# Nano-RS485_RJ45-GW-v1.net
KiCad netlist of a schematic drawn in EAGLE
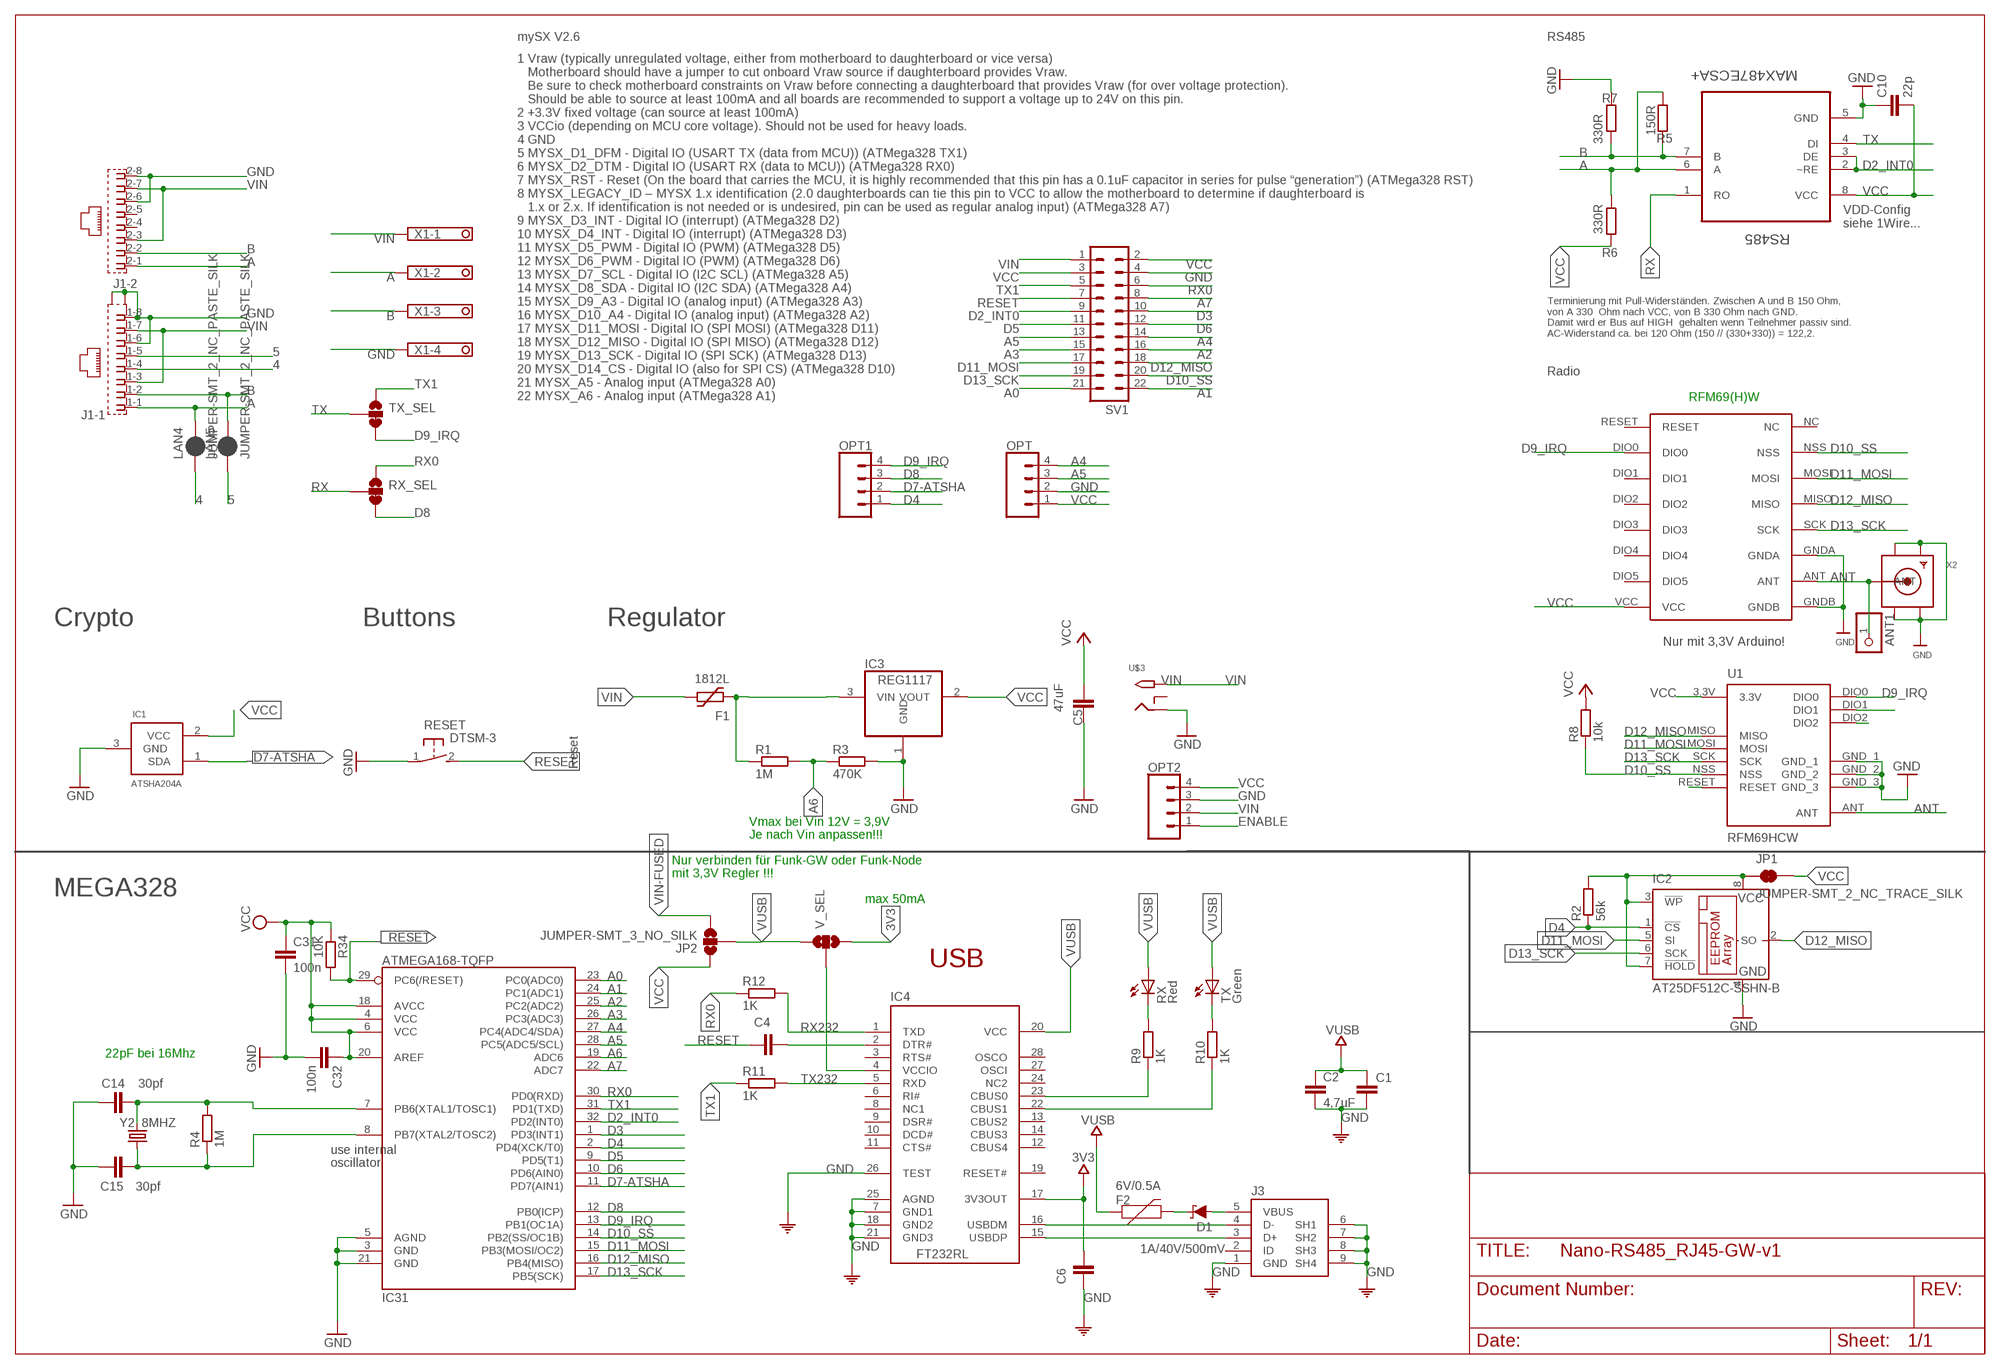
[diagram p0: schematic, sheet 1]

(export (version "E")
  (design (tool "Eeschema 10.0.6"))
  (components
    (comp (ref "ANT1")
      (value "PINHD-1X1")
      (footprint "eagle-import:1X01")
      (libsource (lib "eagle-import") (part "PINHD-1X1"))
    )
    (comp (ref "C1")
      (value "100nF")
      (footprint "eagle-import:C0805")
      (libsource (lib "eagle-import") (part "resistor_348_C-EUC0805"))
    )
    (comp (ref "C2")
      (value "4,7uF")
      (footprint "eagle-import:C1206")
      (libsource (lib "eagle-import") (part "resistor_348_C-EUC1206"))
    )
    (comp (ref "C4")
      (value "100nF")
      (footprint "eagle-import:C0805")
      (libsource (lib "eagle-import") (part "resistor_348_C-EUC0805"))
    )
    (comp (ref "C5")
      (value "47uF")
      (footprint "eagle-import:C1206")
      (libsource (lib "eagle-import") (part "resistor_348_C-EUC1206"))
    )
    (comp (ref "C6")
      (value "100nF")
      (footprint "eagle-import:C0805")
      (libsource (lib "eagle-import") (part "resistor_348_C-EUC0805"))
    )
    (comp (ref "C10")
      (value "22p")
      (footprint "eagle-import:C0805")
      (libsource (lib "eagle-import") (part "C-EUC0805"))
    )
    (comp (ref "C14")
      (value "30pf")
      (footprint "eagle-import:0805")
      (libsource (lib "eagle-import") (part "CAP0805"))
    )
    (comp (ref "C15")
      (value "30pf")
      (footprint "eagle-import:0805")
      (libsource (lib "eagle-import") (part "CAP0805"))
    )
    (comp (ref "C31")
      (value "100n")
      (footprint "eagle-import:C0805")
      (libsource (lib "eagle-import") (part "C-EUC0805"))
    )
    (comp (ref "C32")
      (value "100n")
      (footprint "eagle-import:C0805")
      (libsource (lib "eagle-import") (part "C-EUC0805"))
    )
    (comp (ref "D1")
      (value "1A/40V/500mV")
      (footprint "eagle-import:SMA-DIODE")
      (libsource (lib "eagle-import") (part "DIODE-SCHOTTKY-SS14"))
    )
    (comp (ref "F1")
      (value "1812L")
      (footprint "eagle-import:1812L")
      (libsource (lib "eagle-import") (part "1812L"))
    )
    (comp (ref "F2")
      (value "6V/0.5A")
      (footprint "eagle-import:1206")
      (libsource (lib "eagle-import") (part "PPTC_HALF-AMP"))
    )
    (comp (ref "IC1")
      (value "ATSHA204A")
      (footprint "eagle-import:SOT23")
      (libsource (lib "eagle-import") (part "ATSHA204A"))
    )
    (comp (ref "IC2")
      (value "AT25DF512C-SSHN-B")
      (footprint "eagle-import:SO-08")
      (fields (field (name "MF") "MICROCHIP") (field (name "MPN") "25AA080/SN"))
      (libsource (lib "eagle-import") (part "25SNAA080"))
    )
    (comp (ref "IC3")
      (value "REG1117")
      (footprint "eagle-import:SOT223")
      (libsource (lib "eagle-import") (part "REG1117"))
    )
    (comp (ref "IC4")
      (value "FT232RL")
      (footprint "eagle-import:SSOP28")
      (libsource (lib "eagle-import") (part "0226_FT232RL"))
    )
    (comp (ref "IC31")
      (value "ATMEGA168-TQFP")
      (footprint "eagle-import:TQFP32-08")
      (libsource (lib "eagle-import") (part "ATMEGA168-TQFP"))
    )
    (comp (ref "J1")
      (value "RJ45_2X_NARROW_SHILDPINS_NOCASE")
      (footprint "eagle-import:RJ45_2X_NARROW_SHILDPINS_NOCASE")
      (libsource (lib "eagle-import") (part "RJ45_2X_NARROW_SHILDPINS_NOCASE"))
    )
    (comp (ref "J3")
      (value "0219_14850")
      (footprint "eagle-import:USB-MINI-B_2")
      (fields (field (name "PART_NUMBER") "14850"))
      (libsource (lib "eagle-import") (part "0219_14850"))
    )
    (comp (ref "JP1")
      (value "JUMPER-SMT_2_NC_TRACE_SILK")
      (footprint "eagle-import:SMT-JUMPER_2_NC_TRACE_SILK")
      (libsource (lib "eagle-import") (part "JUMPER-SMT_2_NC_TRACE_SILK"))
    )
    (comp (ref "JP2")
      (value "JUMPER-SMT_3_NO_SILK")
      (footprint "eagle-import:SMT-JUMPER_3_NO_SILK")
      (libsource (lib "eagle-import") (part "JUMPER-SMT_3_NO_SILK"))
    )
    (comp (ref "LAN4")
      (value "JUMPER-SMT_2_NC_PASTE_SILK")
      (footprint "eagle-import:SMT-JUMPER_2_NC_PASTE_SILK")
      (libsource (lib "eagle-import") (part "JUMPER-SMT_2_NC_PASTE_SILK"))
    )
    (comp (ref "LAN5")
      (value "JUMPER-SMT_2_NC_PASTE_SILK")
      (footprint "eagle-import:SMT-JUMPER_2_NC_PASTE_SILK")
      (libsource (lib "eagle-import") (part "JUMPER-SMT_2_NC_PASTE_SILK"))
    )
    (comp (ref "OPT")
      (value "CONN_04")
      (footprint "eagle-import:1X04")
      (libsource (lib "eagle-import") (part "CONN_04"))
    )
    (comp (ref "OPT1")
      (value "CONN_04")
      (footprint "eagle-import:1X04")
      (libsource (lib "eagle-import") (part "CONN_04"))
    )
    (comp (ref "OPT2")
      (value "CONN_04")
      (footprint "eagle-import:1X04")
      (libsource (lib "eagle-import") (part "CONN_04"))
    )
    (comp (ref "R1")
      (value "1M")
      (footprint "eagle-import:M0805")
      (libsource (lib "eagle-import") (part "R-EU_M0805"))
    )
    (comp (ref "R2")
      (value "56k")
      (footprint "eagle-import:M0805")
      (libsource (lib "eagle-import") (part "resistor_R-EU_M0805"))
    )
    (comp (ref "R3")
      (value "470K")
      (footprint "eagle-import:R0805")
      (libsource (lib "eagle-import") (part "R-EU_R0805"))
    )
    (comp (ref "R4")
      (value "1M")
      (footprint "eagle-import:M0805")
      (libsource (lib "eagle-import") (part "R-EU_M0805"))
    )
    (comp (ref "R5")
      (value "150R")
      (footprint "eagle-import:R0805")
      (libsource (lib "eagle-import") (part "R-EU_R0805"))
    )
    (comp (ref "R6")
      (value "330R")
      (footprint "eagle-import:R0805")
      (libsource (lib "eagle-import") (part "R-EU_R0805"))
    )
    (comp (ref "R7")
      (value "330R")
      (footprint "eagle-import:R0805")
      (libsource (lib "eagle-import") (part "R-EU_R0805"))
    )
    (comp (ref "R8")
      (value "10k")
      (footprint "eagle-import:M0805")
      (libsource (lib "eagle-import") (part "R-EU_M0805"))
    )
    (comp (ref "R9")
      (value "1K")
      (footprint "eagle-import:R0805")
      (libsource (lib "eagle-import") (part "resistor_348_R-EU_R0805"))
    )
    (comp (ref "R10")
      (value "1K")
      (footprint "eagle-import:R0805")
      (libsource (lib "eagle-import") (part "resistor_348_R-EU_R0805"))
    )
    (comp (ref "R11")
      (value "1K")
      (footprint "eagle-import:R0805")
      (libsource (lib "eagle-import") (part "resistor_348_R-EU_R0805"))
    )
    (comp (ref "R12")
      (value "1K")
      (footprint "eagle-import:R0805")
      (libsource (lib "eagle-import") (part "resistor_348_R-EU_R0805"))
    )
    (comp (ref "R34")
      (value "10K")
      (footprint "eagle-import:R0805")
      (libsource (lib "eagle-import") (part "R-EU_R0805"))
    )
    (comp (ref "RESET")
      (value "DTSM-3")
      (footprint "eagle-import:DTSM-3")
      (libsource (lib "eagle-import") (part "DTSM-3"))
    )
    (comp (ref "RFM69W")
      (value "RFM69HW")
      (footprint "eagle-import:RFM")
      (libsource (lib "eagle-import") (part "RFM69HW"))
    )
    (comp (ref "RS485")
      (value "MAX487ECSA+")
      (footprint "eagle-import:SOIC127P600X175-8N")
      (libsource (lib "eagle-import") (part "MAX487ECSA+"))
    )
    (comp (ref "RX")
      (value "Red")
      (footprint "eagle-import:CHIPLED_0805")
      (fields (field (name "PART_NUMBER") "KTP-2012SURCK"))
      (libsource (lib "eagle-import") (part "0181_KTP-2012SURCK"))
    )
    (comp (ref "RX_SEL")
      (value "JUMPER-SMT_3_1-NC_TRACE_SILK")
      (footprint "eagle-import:SMT-JUMPER_3_1-NC_TRACE_SILK")
      (libsource (lib "eagle-import") (part "JUMPER-SMT_3_1-NC_TRACE_SILK"))
    )
    (comp (ref "SV1")
      (value "MA11-2")
      (footprint "eagle-import:MA11-2")
      (libsource (lib "eagle-import") (part "MA11-2"))
    )
    (comp (ref "TX")
      (value "Green")
      (footprint "eagle-import:CHIPLED_0805")
      (fields (field (name "PART_NUMBER") "KPT-2012SGC"))
      (libsource (lib "eagle-import") (part "0043_KPT-2012SGC"))
    )
    (comp (ref "TX_SEL")
      (value "JUMPER-SMT_3_1-NC_TRACE_SILK")
      (footprint "eagle-import:SMT-JUMPER_3_1-NC_TRACE_SILK")
      (libsource (lib "eagle-import") (part "JUMPER-SMT_3_1-NC_TRACE_SILK"))
    )
    (comp (ref "U$3")
      (value "2.1MMJACKTHM")
      (footprint "eagle-import:PJ-102A")
      (libsource (lib "eagle-import") (part "2.1MMJACKTHM"))
    )
    (comp (ref "U1")
      (value "RFM69HCW")
      (footprint "eagle-import:RFM69HCW-XXXS2")
      (libsource (lib "eagle-import") (part "RFM69HCW"))
    )
    (comp (ref "V_SEL")
      (value "JUMPER-SMT_3_NO_SILK")
      (footprint "eagle-import:SMT-JUMPER_3_NO_SILK")
      (libsource (lib "eagle-import") (part "JUMPER-SMT_3_NO_SILK"))
    )
    (comp (ref "X1")
      (value "1751264")
      (footprint "eagle-import:1751264")
      (libsource (lib "eagle-import") (part "1751264"))
    )
    (comp (ref "X2")
      (value "SMACONNECTOR_EDGE")
      (footprint "eagle-import:SMA_EDGELAUNCH")
      (libsource (lib "eagle-import") (part "SMACONNECTOR_EDGE"))
    )
    (comp (ref "Y2")
      (value "8MHZ")
      (footprint "eagle-import:CRYSTAL-TXC-7A")
      (libsource (lib "eagle-import") (part "CRYSTALTXC-7A"))
    )
  )
  (nets
    (net (code "1") (name "/4") (class "Default")
      (node (ref "J1") (pin "1-4") (pinfunction "4_1-4") (pintype "passive"))
      (node (ref "LAN4") (pin "1") (pinfunction "1_1") (pintype "passive"))
    )
    (net (code "2") (name "/5") (class "Default")
      (node (ref "J1") (pin "1-5") (pinfunction "5_1-5") (pintype "passive"))
      (node (ref "LAN5") (pin "1") (pinfunction "1_1") (pintype "passive"))
    )
    (net (code "3") (name "/A") (class "Default")
      (node (ref "J1") (pin "1-1") (pinfunction "1_1-1") (pintype "passive"))
      (node (ref "J1") (pin "2-1") (pinfunction "1_2-1") (pintype "passive"))
      (node (ref "LAN4") (pin "2") (pinfunction "2_2") (pintype "passive"))
      (node (ref "R5") (pin "1") (pinfunction "1_1") (pintype "passive"))
      (node (ref "R6") (pin "2") (pinfunction "2_2") (pintype "passive"))
      (node (ref "RS485") (pin "6") (pinfunction "A_6") (pintype "bidirectional"))
      (node (ref "X1") (pin "2") (pinfunction "K_2") (pintype "passive"))
    )
    (net (code "4") (name "/A0") (class "Default")
      (node (ref "IC31") (pin "23") (pinfunction "PC0(ADC0)_23") (pintype "bidirectional"))
      (node (ref "SV1") (pin "21") (pinfunction "21_21") (pintype "passive"))
    )
    (net (code "5") (name "/A1") (class "Default")
      (node (ref "IC31") (pin "24") (pinfunction "PC1(ADC1)_24") (pintype "bidirectional"))
      (node (ref "SV1") (pin "22") (pinfunction "22_22") (pintype "passive"))
    )
    (net (code "6") (name "/A2") (class "Default")
      (node (ref "IC31") (pin "25") (pinfunction "PC2(ADC2)_25") (pintype "bidirectional"))
      (node (ref "SV1") (pin "16") (pinfunction "16_16") (pintype "passive"))
    )
    (net (code "7") (name "/A3") (class "Default")
      (node (ref "IC31") (pin "26") (pinfunction "PC3(ADC3)_26") (pintype "bidirectional"))
      (node (ref "SV1") (pin "15") (pinfunction "15_15") (pintype "passive"))
    )
    (net (code "8") (name "/A4") (class "Default")
      (node (ref "IC31") (pin "27") (pinfunction "PC4(ADC4/SDA)_27") (pintype "bidirectional"))
      (node (ref "OPT") (pin "4") (pinfunction "4_4") (pintype "passive"))
      (node (ref "SV1") (pin "14") (pinfunction "14_14") (pintype "passive"))
    )
    (net (code "9") (name "/A5") (class "Default")
      (node (ref "IC31") (pin "28") (pinfunction "PC5(ADC5/SCL)_28") (pintype "bidirectional"))
      (node (ref "OPT") (pin "3") (pinfunction "3_3") (pintype "passive"))
      (node (ref "SV1") (pin "13") (pinfunction "13_13") (pintype "passive"))
    )
    (net (code "10") (name "/A7") (class "Default")
      (node (ref "IC31") (pin "22") (pinfunction "ADC7_22") (pintype "bidirectional"))
      (node (ref "SV1") (pin "8") (pinfunction "8_8") (pintype "passive"))
    )
    (net (code "11") (name "/ANT") (class "Default")
      (node (ref "ANT1") (pin "1") (pinfunction "1_1") (pintype "passive"))
      (node (ref "RFM69W") (pin "ANT") (pinfunction "ANT_ANT") (pintype "bidirectional"))
      (node (ref "U1") (pin "ANT") (pinfunction "ANT_ANT") (pintype "passive"))
      (node (ref "X2") (pin "P") (pinfunction "ANT_P") (pintype "bidirectional"))
    )
    (net (code "12") (name "/B") (class "Default")
      (node (ref "J1") (pin "1-2") (pinfunction "2_1-2") (pintype "passive"))
      (node (ref "J1") (pin "2-2") (pinfunction "2_2-2") (pintype "passive"))
      (node (ref "LAN5") (pin "2") (pinfunction "2_2") (pintype "passive"))
      (node (ref "R5") (pin "2") (pinfunction "2_2") (pintype "passive"))
      (node (ref "R7") (pin "1") (pinfunction "1_1") (pintype "passive"))
      (node (ref "RS485") (pin "7") (pinfunction "B_7") (pintype "bidirectional"))
      (node (ref "X1") (pin "3") (pinfunction "K_3") (pintype "passive"))
    )
    (net (code "13") (name "/D2_INT0") (class "Default")
      (node (ref "IC31") (pin "32") (pinfunction "PD2(INT0)_32") (pintype "bidirectional"))
      (node (ref "RS485") (pin "2") (pinfunction "~{RE}_2") (pintype "input"))
      (node (ref "RS485") (pin "3") (pinfunction "DE_3") (pintype "input"))
      (node (ref "SV1") (pin "9") (pinfunction "9_9") (pintype "passive"))
    )
    (net (code "14") (name "/D3") (class "Default")
      (node (ref "IC31") (pin "1") (pinfunction "PD3(INT1)_1") (pintype "bidirectional"))
      (node (ref "SV1") (pin "10") (pinfunction "10_10") (pintype "passive"))
    )
    (net (code "15") (name "/D5") (class "Default")
      (node (ref "IC31") (pin "9") (pinfunction "PD5(T1)_9") (pintype "bidirectional"))
      (node (ref "SV1") (pin "11") (pinfunction "11_11") (pintype "passive"))
    )
    (net (code "16") (name "/D6") (class "Default")
      (node (ref "IC31") (pin "10") (pinfunction "PD6(AIN0)_10") (pintype "bidirectional"))
      (node (ref "SV1") (pin "12") (pinfunction "12_12") (pintype "passive"))
    )
    (net (code "17") (name "/D7-ATSHA") (class "Default")
      (node (ref "IC1") (pin "1") (pinfunction "SDA_1") (pintype "bidirectional"))
      (node (ref "IC31") (pin "11") (pinfunction "PD7(AIN1)_11") (pintype "bidirectional"))
      (node (ref "OPT1") (pin "2") (pinfunction "2_2") (pintype "passive"))
    )
    (net (code "18") (name "/D8") (class "Default")
      (node (ref "IC31") (pin "12") (pinfunction "PB0(ICP)_12") (pintype "bidirectional"))
      (node (ref "OPT1") (pin "3") (pinfunction "3_3") (pintype "passive"))
      (node (ref "RX_SEL") (pin "3") (pinfunction "3_3") (pintype "passive"))
    )
    (net (code "19") (name "/D9_IRQ") (class "Default")
      (node (ref "IC31") (pin "13") (pinfunction "PB1(OC1A)_13") (pintype "bidirectional"))
      (node (ref "OPT1") (pin "4") (pinfunction "4_4") (pintype "passive"))
      (node (ref "RFM69W") (pin "DIO0") (pinfunction "DIO0_DIO0") (pintype "bidirectional"))
      (node (ref "TX_SEL") (pin "3") (pinfunction "3_3") (pintype "passive"))
      (node (ref "U1") (pin "DIO0") (pinfunction "DIO0_DIO0") (pintype "bidirectional"))
    )
    (net (code "20") (name "/D10_SS") (class "Default")
      (node (ref "IC31") (pin "14") (pinfunction "PB2(SS/OC1B)_14") (pintype "bidirectional"))
      (node (ref "R8") (pin "1") (pinfunction "1_1") (pintype "passive"))
      (node (ref "RFM69W") (pin "NSS") (pinfunction "NSS_NSS") (pintype "bidirectional"))
      (node (ref "SV1") (pin "20") (pinfunction "20_20") (pintype "passive"))
      (node (ref "U1") (pin "NSS") (pinfunction "NSS_NSS") (pintype "input"))
    )
    (net (code "21") (name "/ENABLE") (class "Default")
      (node (ref "OPT2") (pin "1") (pinfunction "1_1") (pintype "passive"))
    )
    (net (code "22") (name "/RX232") (class "Default")
      (node (ref "IC4") (pin "1") (pinfunction "TXD_1") (pintype "output"))
      (node (ref "R12") (pin "2") (pinfunction "2_2") (pintype "passive"))
    )
    (net (code "23") (name "/TX") (class "Default")
      (node (ref "RS485") (pin "4") (pinfunction "DI_4") (pintype "input"))
      (node (ref "TX_SEL") (pin "2") (pinfunction "2_2") (pintype "passive"))
    )
    (net (code "24") (name "/TX232") (class "Default")
      (node (ref "IC4") (pin "5") (pinfunction "RXD_5") (pintype "input"))
      (node (ref "R11") (pin "2") (pinfunction "2_2") (pintype "passive"))
    )
    (net (code "25") (name "3V3") (class "Default")
      (node (ref "C6") (pin "2") (pinfunction "2_2") (pintype "passive"))
      (node (ref "IC4") (pin "17") (pinfunction "3V3OUT_17") (pintype "power_in"))
      (node (ref "V_SEL") (pin "3") (pinfunction "3_3") (pintype "passive"))
    )
    (net (code "26") (name "A6") (class "Default")
      (node (ref "IC31") (pin "19") (pinfunction "ADC6_19") (pintype "bidirectional"))
      (node (ref "R1") (pin "2") (pinfunction "2_2") (pintype "passive"))
      (node (ref "R3") (pin "1") (pinfunction "1_1") (pintype "passive"))
    )
    (net (code "27") (name "COM") (class "Default")
      (node (ref "C1") (pin "2") (pinfunction "2_2") (pintype "passive"))
      (node (ref "C10") (pin "1") (pinfunction "1_1") (pintype "passive"))
      (node (ref "C14") (pin "1") (pinfunction "1_1") (pintype "passive"))
      (node (ref "C15") (pin "1") (pinfunction "1_1") (pintype "passive"))
      (node (ref "C2") (pin "2") (pinfunction "2_2") (pintype "passive"))
      (node (ref "C31") (pin "2") (pinfunction "2_2") (pintype "passive"))
      (node (ref "C32") (pin "2") (pinfunction "2_2") (pintype "passive"))
      (node (ref "C5") (pin "1") (pinfunction "1_1") (pintype "passive"))
      (node (ref "C6") (pin "1") (pinfunction "1_1") (pintype "passive"))
      (node (ref "IC1") (pin "3") (pinfunction "GND_3") (pintype "bidirectional"))
      (node (ref "IC2") (pin "4") (pinfunction "GND_4") (pintype "power_in"))
      (node (ref "IC3") (pin "1") (pinfunction "GND_1") (pintype "power_in"))
      (node (ref "IC31") (pin "21") (pinfunction "GND_21") (pintype "bidirectional"))
      (node (ref "IC31") (pin "3") (pinfunction "GND_3") (pintype "bidirectional"))
      (node (ref "IC31") (pin "5") (pinfunction "AGND_5") (pintype "bidirectional"))
      (node (ref "IC4") (pin "18") (pinfunction "GND2_18") (pintype "power_in"))
      (node (ref "IC4") (pin "21") (pinfunction "GND3_21") (pintype "power_in"))
      (node (ref "IC4") (pin "25") (pinfunction "AGND_25") (pintype "power_in"))
      (node (ref "IC4") (pin "26") (pinfunction "TEST_26") (pintype "bidirectional"))
      (node (ref "IC4") (pin "7") (pinfunction "GND1_7") (pintype "power_in"))
      (node (ref "J1") (pin "1-6") (pinfunction "6_1-6") (pintype "passive"))
      (node (ref "J1") (pin "1-8") (pinfunction "8_1-8") (pintype "passive"))
      (node (ref "J1") (pin "2-6") (pinfunction "6_2-6") (pintype "passive"))
      (node (ref "J1") (pin "2-8") (pinfunction "8_2-8") (pintype "passive"))
      (node (ref "J1") (pin "G1") (pinfunction "S1_G1") (pintype "passive"))
      (node (ref "J1") (pin "G3") (pinfunction "S2_G3") (pintype "passive"))
      (node (ref "J3") (pin "1") (pinfunction "GND_1") (pintype "passive"))
      (node (ref "J3") (pin "6") (pinfunction "SH1_6") (pintype "passive"))
      (node (ref "J3") (pin "7") (pinfunction "SH2_7") (pintype "passive"))
      (node (ref "J3") (pin "8") (pinfunction "SH3_8") (pintype "passive"))
      (node (ref "J3") (pin "9") (pinfunction "SH4_9") (pintype "passive"))
      (node (ref "OPT") (pin "2") (pinfunction "2_2") (pintype "passive"))
      (node (ref "OPT2") (pin "3") (pinfunction "3_3") (pintype "passive"))
      (node (ref "R3") (pin "2") (pinfunction "2_2") (pintype "passive"))
      (node (ref "R7") (pin "2") (pinfunction "2_2") (pintype "passive"))
      (node (ref "RESET") (pin "1") (pinfunction "1_1") (pintype "passive"))
      (node (ref "RFM69W") (pin "GNDA") (pinfunction "GNDA_GNDA") (pintype "bidirectional"))
      (node (ref "RFM69W") (pin "GNDB") (pinfunction "GNDB_GNDB") (pintype "bidirectional"))
      (node (ref "RS485") (pin "5") (pinfunction "GND_5") (pintype "passive"))
      (node (ref "SV1") (pin "4") (pinfunction "4_4") (pintype "passive"))
      (node (ref "U$3") (pin "RING") (pinfunction "RING_RING") (pintype "bidirectional"))
      (node (ref "U1") (pin "GND_1") (pinfunction "GND_1_GND_1") (pintype "power_in"))
      (node (ref "U1") (pin "GND_2") (pinfunction "GND_2_GND_2") (pintype "power_in"))
      (node (ref "U1") (pin "GND_3") (pinfunction "GND_3_GND_3") (pintype "power_in"))
      (node (ref "X1") (pin "4") (pinfunction "K_4") (pintype "passive"))
      (node (ref "X2") (pin "GND@1") (pinfunction "GND4_GND@1") (pintype "power_in"))
      (node (ref "X2") (pin "GND@2") (pinfunction "GND3_GND@2") (pintype "power_in"))
      (node (ref "X2") (pin "GND@3") (pinfunction "GND2_GND@3") (pintype "power_in"))
      (node (ref "X2") (pin "GND@4") (pinfunction "GND1_GND@4") (pintype "power_in"))
    )
    (net (code "28") (name "D4") (class "Default")
      (node (ref "IC2") (pin "1") (pinfunction "~{CS}_1") (pintype "input"))
      (node (ref "IC31") (pin "2") (pinfunction "PD4(XCK/T0)_2") (pintype "bidirectional"))
      (node (ref "OPT1") (pin "1") (pinfunction "1_1") (pintype "passive"))
      (node (ref "R2") (pin "1") (pinfunction "1_1") (pintype "passive"))
    )
    (net (code "29") (name "D11_MOSI") (class "Default")
      (node (ref "IC2") (pin "5") (pinfunction "SI_5") (pintype "input"))
      (node (ref "IC31") (pin "15") (pinfunction "PB3(MOSI/OC2)_15") (pintype "bidirectional"))
      (node (ref "RFM69W") (pin "MOSI") (pinfunction "MOSI_MOSI") (pintype "bidirectional"))
      (node (ref "SV1") (pin "17") (pinfunction "17_17") (pintype "passive"))
      (node (ref "U1") (pin "MOSI") (pinfunction "MOSI_MOSI") (pintype "input"))
    )
    (net (code "30") (name "D12_MISO") (class "Default")
      (node (ref "IC2") (pin "2") (pinfunction "SO_2") (pintype "bidirectional"))
      (node (ref "IC31") (pin "16") (pinfunction "PB4(MISO)_16") (pintype "bidirectional"))
      (node (ref "RFM69W") (pin "MISO") (pinfunction "MISO_MISO") (pintype "bidirectional"))
      (node (ref "SV1") (pin "18") (pinfunction "18_18") (pintype "passive"))
      (node (ref "U1") (pin "MISO") (pinfunction "MISO_MISO") (pintype "bidirectional"))
    )
    (net (code "31") (name "D13_SCK") (class "Default")
      (node (ref "IC2") (pin "6") (pinfunction "SCK_6") (pintype "input"))
      (node (ref "IC31") (pin "17") (pinfunction "PB5(SCK)_17") (pintype "bidirectional"))
      (node (ref "RFM69W") (pin "SCK") (pinfunction "SCK_SCK") (pintype "bidirectional"))
      (node (ref "SV1") (pin "19") (pinfunction "19_19") (pintype "passive"))
      (node (ref "U1") (pin "SCK") (pinfunction "SCK_SCK") (pintype "input"))
    )
    (net (code "32") (name "Net-(D1-PadC)") (class "Default")
      (node (ref "D1") (pin "C") (pinfunction "C_C") (pintype "passive"))
      (node (ref "F2") (pin "2") (pinfunction "2_2") (pintype "bidirectional"))
    )
    (net (code "33") (name "Net-(IC2-VCC)") (class "Default")
      (node (ref "IC2") (pin "3") (pinfunction "~{WP}_3") (pintype "input"))
      (node (ref "IC2") (pin "7") (pinfunction "~{HOLD}_7") (pintype "input"))
      (node (ref "IC2") (pin "8") (pinfunction "VCC_8") (pintype "power_in"))
      (node (ref "JP1") (pin "1") (pinfunction "1_1") (pintype "passive"))
      (node (ref "R2") (pin "2") (pinfunction "2_2") (pintype "passive"))
    )
    (net (code "34") (name "Net-(IC4-CBUS0)") (class "Default")
      (node (ref "IC4") (pin "23") (pinfunction "CBUS0_23") (pintype "bidirectional"))
      (node (ref "R9") (pin "1") (pinfunction "1_1") (pintype "passive"))
    )
    (net (code "35") (name "Net-(IC4-CBUS1)") (class "Default")
      (node (ref "IC4") (pin "22") (pinfunction "CBUS1_22") (pintype "bidirectional"))
      (node (ref "R10") (pin "1") (pinfunction "1_1") (pintype "passive"))
    )
    (net (code "36") (name "Net-(IC4-DTR#)") (class "Default")
      (node (ref "C4") (pin "2") (pinfunction "2_2") (pintype "passive"))
      (node (ref "IC4") (pin "2") (pinfunction "DTR#_2") (pintype "output"))
    )
    (net (code "37") (name "Net-(IC4-USBDM)") (class "Default")
      (node (ref "IC4") (pin "16") (pinfunction "USBDM_16") (pintype "bidirectional"))
      (node (ref "J3") (pin "4") (pinfunction "D-_4") (pintype "bidirectional"))
    )
    (net (code "38") (name "Net-(IC4-USBDP)") (class "Default")
      (node (ref "IC4") (pin "15") (pinfunction "USBDP_15") (pintype "bidirectional"))
      (node (ref "J3") (pin "3") (pinfunction "D+_3") (pintype "bidirectional"))
    )
    (net (code "39") (name "Net-(IC4-VCCIO)") (class "Default")
      (node (ref "IC4") (pin "4") (pinfunction "VCCIO_4") (pintype "power_in"))
      (node (ref "V_SEL") (pin "2") (pinfunction "2_2") (pintype "passive"))
    )
    (net (code "40") (name "Net-(IC31-PB6(XTAL1{slash}TOSC1))") (class "Default")
      (node (ref "C14") (pin "2") (pinfunction "2_2") (pintype "passive"))
      (node (ref "IC31") (pin "7") (pinfunction "PB6(XTAL1/TOSC1)_7") (pintype "bidirectional"))
      (node (ref "R4") (pin "2") (pinfunction "2_2") (pintype "passive"))
      (node (ref "Y2") (pin "P$2") (pinfunction "2_P$2") (pintype "passive"))
    )
    (net (code "41") (name "Net-(IC31-PB7(XTAL2{slash}TOSC2))") (class "Default")
      (node (ref "C15") (pin "2") (pinfunction "2_2") (pintype "passive"))
      (node (ref "IC31") (pin "8") (pinfunction "PB7(XTAL2/TOSC2)_8") (pintype "bidirectional"))
      (node (ref "R4") (pin "1") (pinfunction "1_1") (pintype "passive"))
      (node (ref "Y2") (pin "P$1") (pinfunction "1_P$1") (pintype "passive"))
    )
    (net (code "42") (name "Net-(J3-VBUS)") (class "Default")
      (node (ref "D1") (pin "A") (pinfunction "A_A") (pintype "passive"))
      (node (ref "J3") (pin "5") (pinfunction "VBUS_5") (pintype "power_in"))
    )
    (net (code "43") (name "Net-(R9-Pad2)") (class "Default")
      (node (ref "R9") (pin "2") (pinfunction "2_2") (pintype "passive"))
      (node (ref "RX") (pin "C") (pinfunction "C_C") (pintype "passive"))
    )
    (net (code "44") (name "Net-(R10-Pad2)") (class "Default")
      (node (ref "R10") (pin "2") (pinfunction "2_2") (pintype "passive"))
      (node (ref "TX") (pin "C") (pinfunction "C_C") (pintype "passive"))
    )
    (net (code "45") (name "RESET") (class "Default")
      (node (ref "C4") (pin "1") (pinfunction "1_1") (pintype "passive"))
      (node (ref "IC31") (pin "29") (pinfunction "PC6(/RESET)_29") (pintype "bidirectional"))
      (node (ref "R34") (pin "2") (pinfunction "2_2") (pintype "passive"))
      (node (ref "RESET") (pin "2") (pinfunction "2_2") (pintype "passive"))
      (node (ref "SV1") (pin "7") (pinfunction "7_7") (pintype "passive"))
    )
    (net (code "46") (name "RX") (class "Default")
      (node (ref "RS485") (pin "1") (pinfunction "RO_1") (pintype "output"))
      (node (ref "RX_SEL") (pin "2") (pinfunction "2_2") (pintype "passive"))
    )
    (net (code "47") (name "RX0") (class "Default")
      (node (ref "IC31") (pin "30") (pinfunction "PD0(RXD)_30") (pintype "bidirectional"))
      (node (ref "R12") (pin "1") (pinfunction "1_1") (pintype "passive"))
      (node (ref "RX_SEL") (pin "1") (pinfunction "1_1") (pintype "passive"))
      (node (ref "SV1") (pin "6") (pinfunction "6_6") (pintype "passive"))
    )
    (net (code "48") (name "TX1") (class "Default")
      (node (ref "IC31") (pin "31") (pinfunction "PD1(TXD)_31") (pintype "bidirectional"))
      (node (ref "R11") (pin "1") (pinfunction "1_1") (pintype "passive"))
      (node (ref "SV1") (pin "5") (pinfunction "5_5") (pintype "passive"))
      (node (ref "TX_SEL") (pin "1") (pinfunction "1_1") (pintype "passive"))
    )
    (net (code "49") (name "VCC") (class "Default")
      (node (ref "C10") (pin "2") (pinfunction "2_2") (pintype "passive"))
      (node (ref "C31") (pin "1") (pinfunction "1_1") (pintype "passive"))
      (node (ref "C32") (pin "1") (pinfunction "1_1") (pintype "passive"))
      (node (ref "C5") (pin "2") (pinfunction "2_2") (pintype "passive"))
      (node (ref "IC1") (pin "2") (pinfunction "VCC_2") (pintype "bidirectional"))
      (node (ref "IC3") (pin "2") (pinfunction "VOUT_2") (pintype "output"))
      (node (ref "IC31") (pin "18") (pinfunction "AVCC_18") (pintype "bidirectional"))
      (node (ref "IC31") (pin "20") (pinfunction "AREF_20") (pintype "bidirectional"))
      (node (ref "IC31") (pin "4") (pinfunction "VCC_4") (pintype "bidirectional"))
      (node (ref "IC31") (pin "6") (pinfunction "VCC_6") (pintype "bidirectional"))
      (node (ref "JP1") (pin "2") (pinfunction "2_2") (pintype "passive"))
      (node (ref "JP2") (pin "1") (pinfunction "1_1") (pintype "passive"))
      (node (ref "OPT") (pin "1") (pinfunction "1_1") (pintype "passive"))
      (node (ref "OPT2") (pin "4") (pinfunction "4_4") (pintype "passive"))
      (node (ref "R34") (pin "1") (pinfunction "1_1") (pintype "passive"))
      (node (ref "R6") (pin "1") (pinfunction "1_1") (pintype "passive"))
      (node (ref "R8") (pin "2") (pinfunction "2_2") (pintype "passive"))
      (node (ref "RFM69W") (pin "VCC") (pinfunction "VCC_VCC") (pintype "bidirectional"))
      (node (ref "RS485") (pin "8") (pinfunction "VCC_8") (pintype "power_in"))
      (node (ref "SV1") (pin "2") (pinfunction "2_2") (pintype "passive"))
      (node (ref "SV1") (pin "3") (pinfunction "3_3") (pintype "passive"))
      (node (ref "U1") (pin "3.3V") (pinfunction "3.3V_3.3V") (pintype "power_in"))
    )
    (net (code "50") (name "VIN") (class "Default")
      (node (ref "F1") (pin "P$2") (pinfunction "2_P$2") (pintype "passive"))
      (node (ref "J1") (pin "1-3") (pinfunction "3_1-3") (pintype "passive"))
      (node (ref "J1") (pin "1-7") (pinfunction "7_1-7") (pintype "passive"))
      (node (ref "J1") (pin "2-3") (pinfunction "3_2-3") (pintype "passive"))
      (node (ref "J1") (pin "2-7") (pinfunction "7_2-7") (pintype "passive"))
      (node (ref "OPT2") (pin "2") (pinfunction "2_2") (pintype "passive"))
      (node (ref "SV1") (pin "1") (pinfunction "1_1") (pintype "passive"))
      (node (ref "U$3") (pin "TIP") (pinfunction "TIP_TIP") (pintype "bidirectional"))
      (node (ref "X1") (pin "1") (pinfunction "K_1") (pintype "passive"))
    )
    (net (code "51") (name "VIN-FUSED") (class "Default")
      (node (ref "F1") (pin "P$1") (pinfunction "1_P$1") (pintype "passive"))
      (node (ref "IC3") (pin "3") (pinfunction "VIN_3") (pintype "input"))
      (node (ref "JP2") (pin "3") (pinfunction "3_3") (pintype "passive"))
      (node (ref "R1") (pin "1") (pinfunction "1_1") (pintype "passive"))
    )
    (net (code "52") (name "VUSB") (class "Default")
      (node (ref "C1") (pin "1") (pinfunction "1_1") (pintype "passive"))
      (node (ref "C2") (pin "1") (pinfunction "1_1") (pintype "passive"))
      (node (ref "F2") (pin "1") (pinfunction "1_1") (pintype "bidirectional"))
      (node (ref "IC4") (pin "20") (pinfunction "VCC_20") (pintype "power_in"))
      (node (ref "JP2") (pin "2") (pinfunction "2_2") (pintype "passive"))
      (node (ref "RX") (pin "A") (pinfunction "A_A") (pintype "passive"))
      (node (ref "TX") (pin "A") (pinfunction "A_A") (pintype "passive"))
      (node (ref "V_SEL") (pin "1") (pinfunction "1_1") (pintype "passive"))
    )
    (net (code "53") (name "unconnected-(IC4-CBUS2-Pad13)") (class "Default")
      (node (ref "IC4") (pin "13") (pinfunction "CBUS2_13") (pintype "bidirectional"))
    )
    (net (code "54") (name "unconnected-(IC4-CBUS3-Pad14)") (class "Default")
      (node (ref "IC4") (pin "14") (pinfunction "CBUS3_14") (pintype "bidirectional"))
    )
    (net (code "55") (name "unconnected-(IC4-CBUS4-Pad12)") (class "Default")
      (node (ref "IC4") (pin "12") (pinfunction "CBUS4_12") (pintype "bidirectional"))
    )
    (net (code "56") (name "unconnected-(IC4-CTS#-Pad11)") (class "Default")
      (node (ref "IC4") (pin "11") (pinfunction "CTS#_11") (pintype "bidirectional"))
    )
    (net (code "57") (name "unconnected-(IC4-DCD#-Pad10)") (class "Default")
      (node (ref "IC4") (pin "10") (pinfunction "DCD#_10") (pintype "bidirectional"))
    )
    (net (code "58") (name "unconnected-(IC4-DSR#-Pad9)") (class "Default")
      (node (ref "IC4") (pin "9") (pinfunction "DSR#_9") (pintype "bidirectional"))
    )
    (net (code "59") (name "unconnected-(IC4-NC1-Pad8)") (class "Default")
      (node (ref "IC4") (pin "8") (pinfunction "NC1_8") (pintype "bidirectional"))
    )
    (net (code "60") (name "unconnected-(IC4-NC2-Pad24)") (class "Default")
      (node (ref "IC4") (pin "24") (pinfunction "NC2_24") (pintype "no_connect"))
    )
    (net (code "61") (name "unconnected-(IC4-OSCI-Pad27)") (class "Default")
      (node (ref "IC4") (pin "27") (pinfunction "OSCI_27") (pintype "bidirectional"))
    )
    (net (code "62") (name "unconnected-(IC4-OSCO-Pad28)") (class "Default")
      (node (ref "IC4") (pin "28") (pinfunction "OSCO_28") (pintype "output"))
    )
    (net (code "63") (name "unconnected-(IC4-RESET#-Pad19)") (class "Default")
      (node (ref "IC4") (pin "19") (pinfunction "RESET#_19") (pintype "bidirectional"))
    )
    (net (code "64") (name "unconnected-(IC4-RI#-Pad6)") (class "Default")
      (node (ref "IC4") (pin "6") (pinfunction "RI#_6") (pintype "bidirectional"))
    )
    (net (code "65") (name "unconnected-(IC4-RTS#-Pad3)") (class "Default")
      (node (ref "IC4") (pin "3") (pinfunction "RTS#_3") (pintype "output"))
    )
    (net (code "66") (name "unconnected-(J1B-4-Pad2-4)") (class "Default")
      (node (ref "J1") (pin "2-4") (pinfunction "4_2-4") (pintype "passive"))
    )
    (net (code "67") (name "unconnected-(J1B-5-Pad2-5)") (class "Default")
      (node (ref "J1") (pin "2-5") (pinfunction "5_2-5") (pintype "passive"))
    )
    (net (code "68") (name "unconnected-(J3-ID-Pad2)") (class "Default")
      (node (ref "J3") (pin "2") (pinfunction "ID_2") (pintype "bidirectional"))
    )
    (net (code "69") (name "unconnected-(RFM69W-PadDIO1)") (class "Default")
      (node (ref "RFM69W") (pin "DIO1") (pinfunction "DIO1_DIO1") (pintype "bidirectional"))
    )
    (net (code "70") (name "unconnected-(RFM69W-PadDIO2)") (class "Default")
      (node (ref "RFM69W") (pin "DIO2") (pinfunction "DIO2_DIO2") (pintype "bidirectional"))
    )
    (net (code "71") (name "unconnected-(RFM69W-PadDIO3)") (class "Default")
      (node (ref "RFM69W") (pin "DIO3") (pinfunction "DIO3_DIO3") (pintype "bidirectional"))
    )
    (net (code "72") (name "unconnected-(RFM69W-PadDIO4)") (class "Default")
      (node (ref "RFM69W") (pin "DIO4") (pinfunction "DIO4_DIO4") (pintype "bidirectional"))
    )
    (net (code "73") (name "unconnected-(RFM69W-PadDIO5)") (class "Default")
      (node (ref "RFM69W") (pin "DIO5") (pinfunction "DIO5_DIO5") (pintype "bidirectional"))
    )
    (net (code "74") (name "unconnected-(RFM69W-PadNC)") (class "Default")
      (node (ref "RFM69W") (pin "NC") (pinfunction "NC_NC") (pintype "bidirectional"))
    )
    (net (code "75") (name "unconnected-(RFM69W-PadRESET)") (class "Default")
      (node (ref "RFM69W") (pin "RESET") (pinfunction "RESET_RESET") (pintype "bidirectional"))
    )
    (net (code "76") (name "unconnected-(U$3-PadRING_SW)") (class "Default")
      (node (ref "U$3") (pin "RING_SW") (pinfunction "RING_SW_RING_SW") (pintype "bidirectional"))
    )
    (net (code "77") (name "unconnected-(U1-PadDIO1)") (class "Default")
      (node (ref "U1") (pin "DIO1") (pinfunction "DIO1_DIO1") (pintype "bidirectional"))
    )
    (net (code "78") (name "unconnected-(U1-PadDIO2)") (class "Default")
      (node (ref "U1") (pin "DIO2") (pinfunction "DIO2_DIO2") (pintype "bidirectional"))
    )
    (net (code "79") (name "unconnected-(U1-PadRESET)") (class "Default")
      (node (ref "U1") (pin "RESET") (pinfunction "RESET_RESET") (pintype "input"))
    )
  )
)
